# Photoreciever.net
KiCad netlist of a schematic drawn in Altium Designer
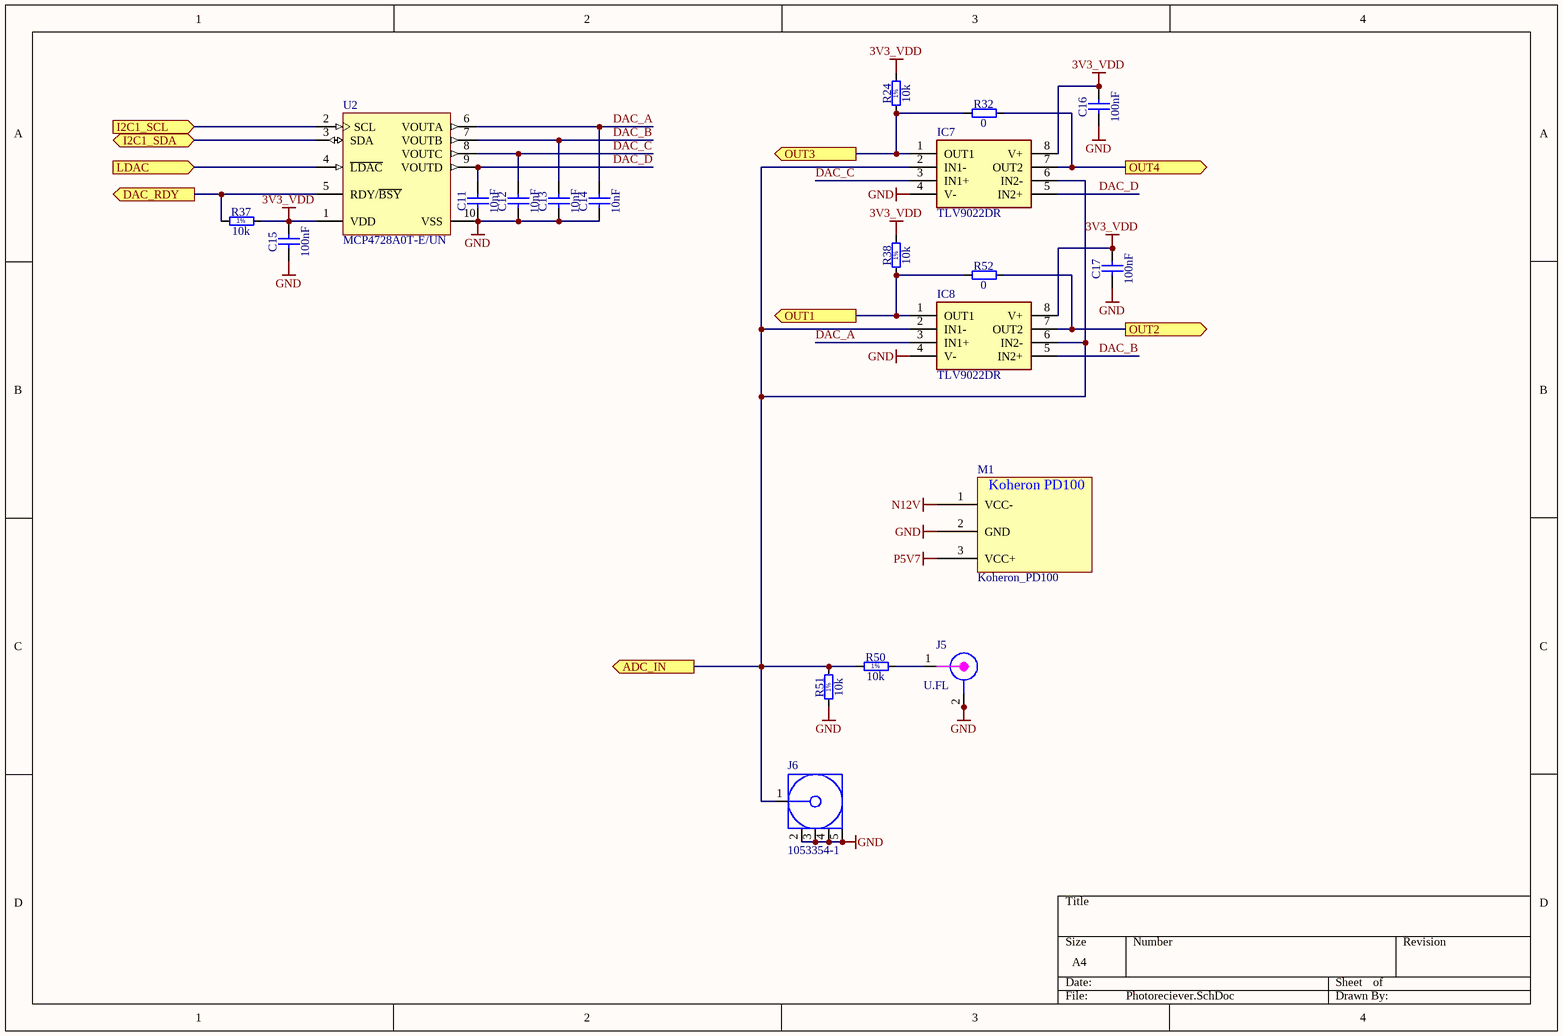
[diagram p0: Photoreciever.SchDoc]

(export (version "E")
  (design (tool "Eeschema 10.0.6"))
  (components
    (comp (ref "C11")
      (value "10nF")
      (footprint "CAPC1005X55N")
      (description "Non-polarised capacitor")
      (fields
        (field (name "PART NUMBER") "CC0402_10NF_16V_10%_X7R")
        (field (name "VOLTAGE") "16V")
        (field (name "AUTHOR") "CERN DEM JLC")
      )
      (libsource (lib "Capacitors") (part "Capacitor - non polarized"))
    )
    (comp (ref "C12")
      (value "10nF")
      (footprint "CAPC1005X55N")
      (description "Non-polarised capacitor")
      (fields
        (field (name "PART NUMBER") "CC0402_10NF_16V_10%_X7R")
        (field (name "VOLTAGE") "16V")
        (field (name "AUTHOR") "CERN DEM JLC")
      )
      (libsource (lib "Capacitors") (part "Capacitor - non polarized"))
    )
    (comp (ref "C13")
      (value "10nF")
      (footprint "CAPC1005X55N")
      (description "Non-polarised capacitor")
      (fields
        (field (name "PART NUMBER") "CC0402_10NF_16V_10%_X7R")
        (field (name "VOLTAGE") "16V")
        (field (name "AUTHOR") "CERN DEM JLC")
      )
      (libsource (lib "Capacitors") (part "Capacitor - non polarized"))
    )
    (comp (ref "C14")
      (value "10nF")
      (footprint "CAPC1005X55N")
      (description "Non-polarised capacitor")
      (fields
        (field (name "PART NUMBER") "CC0402_10NF_16V_10%_X7R")
        (field (name "VOLTAGE") "16V")
        (field (name "AUTHOR") "CERN DEM JLC")
      )
      (libsource (lib "Capacitors") (part "Capacitor - non polarized"))
    )
    (comp (ref "C15")
      (value "100nF")
      (footprint "CAPC1005X55N")
      (description "Non-polarised capacitor")
      (fields
        (field (name "PART NUMBER") "CC0402_100NF_16V_10%_X7R")
        (field (name "VOLTAGE") "16V")
        (field (name "AUTHOR") "CERN DEM JLC")
      )
      (libsource (lib "Capacitors") (part "Capacitor - non polarized"))
    )
    (comp (ref "C16")
      (value "100nF")
      (footprint "CAPC1005X55N")
      (description "Non-polarised capacitor")
      (fields
        (field (name "PART NUMBER") "CC0402_100NF_16V_10%_X7R")
        (field (name "VOLTAGE") "16V")
        (field (name "AUTHOR") "CERN DEM JLC")
      )
      (libsource (lib "Capacitors") (part "Capacitor - non polarized"))
    )
    (comp (ref "C17")
      (value "100nF")
      (footprint "CAPC1005X55N")
      (description "Non-polarised capacitor")
      (fields
        (field (name "PART NUMBER") "CC0402_100NF_16V_10%_X7R")
        (field (name "VOLTAGE") "16V")
        (field (name "AUTHOR") "CERN DEM JLC")
      )
      (libsource (lib "Capacitors") (part "Capacitor - non polarized"))
    )
    (comp (ref "IC7")
      (value "TLV9022DR")
      (footprint "SamacSys:SOIC127P600X175-8N")
      (description "Integrated Circuit")
      (libsource (lib "*") (part "TLV9022DR"))
    )
    (comp (ref "IC8")
      (value "TLV9022DR")
      (footprint "SamacSys:SOIC127P600X175-8N")
      (description "Integrated Circuit")
      (libsource (lib "*") (part "TLV9022DR"))
    )
    (comp (ref "J5")
      (value "U.FL")
      (footprint "CON_UFL_HIROSE_RECEPTACLE")
      (description "UFL")
      (libsource (lib "LIBRARY_SCH") (part "CON_UFL_SMD"))
    )
    (comp (ref "J6")
      (value "1053354-1")
      (footprint "TECO-1053354-1_V")
      (description "Female Coaxial Connector, Pitch 2.55 mm, Height 9.5 mm, Tail Length 3.9 mm, RoHS, Bulk")
      (fields (field (name "MANUFACTURER") "TE Connectivity"))
      (libsource (lib "Altium Content Vault") (part "CN-S-4F-RF5"))
    )
    (comp (ref "M1")
      (value "Koheron_PD100")
      (footprint "Koheron_PD100")
      (libsource (lib "MG_lib") (part "Koheron_PD100"))
    )
    (comp (ref "R24")
      (value "10k")
      (footprint "RESC1005X40N")
      (description "Resistor - 1%")
      (fields
        (field (name "PART NUMBER") "R0402_10K_1%_0.0625W_100PPM")
        (field (name "POWER") "0.0625W")
        (field (name "AUTHOR") "CERN DEM JLC")
      )
      (libsource (lib "Resistors") (part "Resistor - 1%"))
    )
    (comp (ref "R32")
      (value "0")
      (footprint "RESC1005X40N")
      (description "Resistor")
      (fields
        (field (name "PART NUMBER") "R0402_0R_JUMPER")
        (field (name "MANUFACTURER") "GENERIC")
        (field (name "AUTHOR") "CERN DEM JLC")
      )
      (libsource (lib "Resistors") (part "Resistor"))
    )
    (comp (ref "R37")
      (value "10k")
      (footprint "RESC1005X40N")
      (description "Resistor - 1%")
      (fields
        (field (name "PART NUMBER") "R0402_10K_1%_0.0625W_100PPM")
        (field (name "POWER") "0.0625W")
        (field (name "AUTHOR") "CERN DEM JLC")
      )
      (libsource (lib "Resistors") (part "Resistor - 1%"))
    )
    (comp (ref "R38")
      (value "10k")
      (footprint "RESC1005X40N")
      (description "Resistor - 1%")
      (fields
        (field (name "PART NUMBER") "R0402_10K_1%_0.0625W_100PPM")
        (field (name "POWER") "0.0625W")
        (field (name "AUTHOR") "CERN DEM JLC")
      )
      (libsource (lib "Resistors") (part "Resistor - 1%"))
    )
    (comp (ref "R50")
      (value "10k")
      (footprint "RESC1005X40N")
      (description "Resistor - 1%")
      (fields
        (field (name "PART NUMBER") "R0402_10K_1%_0.0625W_100PPM")
        (field (name "POWER") "0.0625W")
        (field (name "AUTHOR") "CERN DEM JLC")
      )
      (libsource (lib "Resistors") (part "Resistor - 1%"))
    )
    (comp (ref "R51")
      (value "10k")
      (footprint "RESC1005X40N")
      (description "Resistor - 1%")
      (fields
        (field (name "PART NUMBER") "R0402_10K_1%_0.0625W_100PPM")
        (field (name "POWER") "0.0625W")
        (field (name "AUTHOR") "CERN DEM JLC")
      )
      (libsource (lib "Resistors") (part "Resistor - 1%"))
    )
    (comp (ref "R52")
      (value "0")
      (footprint "RESC1005X40N")
      (description "Resistor")
      (fields
        (field (name "PART NUMBER") "R0402_0R_JUMPER")
        (field (name "MANUFACTURER") "GENERIC")
        (field (name "AUTHOR") "CERN DEM JLC")
      )
      (libsource (lib "Resistors") (part "Resistor"))
    )
    (comp (ref "U2")
      (value "MCP4728A0T-E/UN")
      (footprint "MSOP-UN10_M")
      (libsource (lib "Altium Content Vault") (part "CON-DAC-MCP4728-10"))
    )
  )
  (nets
    (net (code "1") (name "/ADC_IN") (class "Default")
      (node (ref "IC7") (pin "2") (pinfunction "IN1-_2") (pintype "passive"))
      (node (ref "IC7") (pin "6") (pinfunction "IN2-_6") (pintype "passive"))
      (node (ref "IC8") (pin "2") (pinfunction "IN1-_2") (pintype "passive"))
      (node (ref "IC8") (pin "6") (pinfunction "IN2-_6") (pintype "passive"))
      (node (ref "J6") (pin "1") (pinfunction "1_1") (pintype "passive"))
      (node (ref "R50") (pin "1") (pinfunction "1_1") (pintype "passive"))
      (node (ref "R51") (pin "2") (pinfunction "2_2") (pintype "passive"))
    )
    (net (code "2") (name "/DAC_A") (class "Default")
      (node (ref "C14") (pin "2") (pinfunction "2_2") (pintype "passive"))
      (node (ref "IC8") (pin "3") (pinfunction "IN1+_3") (pintype "passive"))
      (node (ref "U2") (pin "6") (pinfunction "VOUTA_6") (pintype "output"))
    )
    (net (code "3") (name "/DAC_B") (class "Default")
      (node (ref "C13") (pin "2") (pinfunction "2_2") (pintype "passive"))
      (node (ref "IC8") (pin "5") (pinfunction "IN2+_5") (pintype "passive"))
      (node (ref "U2") (pin "7") (pinfunction "VOUTB_7") (pintype "output"))
    )
    (net (code "4") (name "/DAC_C") (class "Default")
      (node (ref "C12") (pin "2") (pinfunction "2_2") (pintype "passive"))
      (node (ref "IC7") (pin "3") (pinfunction "IN1+_3") (pintype "passive"))
      (node (ref "U2") (pin "8") (pinfunction "VOUTC_8") (pintype "output"))
    )
    (net (code "5") (name "/DAC_D") (class "Default")
      (node (ref "C11") (pin "2") (pinfunction "2_2") (pintype "passive"))
      (node (ref "IC7") (pin "5") (pinfunction "IN2+_5") (pintype "passive"))
      (node (ref "U2") (pin "9") (pinfunction "VOUTD_9") (pintype "output"))
    )
    (net (code "6") (name "/DAC_RDY") (class "Default")
      (node (ref "R37") (pin "1") (pinfunction "1_1") (pintype "passive"))
      (node (ref "U2") (pin "5") (pinfunction "RDY/~{BSY}_5") (pintype "open_collector"))
    )
    (net (code "7") (name "/I2C1_SCL") (class "Default")
      (node (ref "U2") (pin "2") (pinfunction "SCL_2") (pintype "input"))
    )
    (net (code "8") (name "/I2C1_SDA") (class "Default")
      (node (ref "U2") (pin "3") (pinfunction "SDA_3") (pintype "bidirectional"))
    )
    (net (code "9") (name "/LDAC") (class "Default")
      (node (ref "U2") (pin "4") (pinfunction "~{LDAC}_4") (pintype "input"))
    )
    (net (code "10") (name "/OUT1") (class "Default")
      (node (ref "IC8") (pin "1") (pinfunction "OUT1_1") (pintype "passive"))
      (node (ref "R38") (pin "1") (pinfunction "1_1") (pintype "passive"))
      (node (ref "R52") (pin "1") (pinfunction "1_1") (pintype "passive"))
    )
    (net (code "11") (name "/OUT2") (class "Default")
      (node (ref "IC8") (pin "7") (pinfunction "OUT2_7") (pintype "passive"))
      (node (ref "R52") (pin "2") (pinfunction "2_2") (pintype "passive"))
    )
    (net (code "12") (name "/OUT3") (class "Default")
      (node (ref "IC7") (pin "1") (pinfunction "OUT1_1") (pintype "passive"))
      (node (ref "R24") (pin "1") (pinfunction "1_1") (pintype "passive"))
      (node (ref "R32") (pin "1") (pinfunction "1_1") (pintype "passive"))
    )
    (net (code "13") (name "/OUT4") (class "Default")
      (node (ref "IC7") (pin "7") (pinfunction "OUT2_7") (pintype "passive"))
      (node (ref "R32") (pin "2") (pinfunction "2_2") (pintype "passive"))
    )
    (net (code "14") (name "3V3_VDD") (class "Default")
      (node (ref "C15") (pin "2") (pinfunction "2_2") (pintype "passive"))
      (node (ref "C16") (pin "2") (pinfunction "2_2") (pintype "passive"))
      (node (ref "C17") (pin "2") (pinfunction "2_2") (pintype "passive"))
      (node (ref "IC7") (pin "8") (pinfunction "V+_8") (pintype "passive"))
      (node (ref "IC8") (pin "8") (pinfunction "V+_8") (pintype "passive"))
      (node (ref "R24") (pin "2") (pinfunction "2_2") (pintype "passive"))
      (node (ref "R37") (pin "2") (pinfunction "2_2") (pintype "passive"))
      (node (ref "R38") (pin "2") (pinfunction "2_2") (pintype "passive"))
      (node (ref "U2") (pin "1") (pinfunction "VDD_1") (pintype "power_in"))
    )
    (net (code "15") (name "GND") (class "Default")
      (node (ref "C11") (pin "1") (pinfunction "1_1") (pintype "passive"))
      (node (ref "C12") (pin "1") (pinfunction "1_1") (pintype "passive"))
      (node (ref "C13") (pin "1") (pinfunction "1_1") (pintype "passive"))
      (node (ref "C14") (pin "1") (pinfunction "1_1") (pintype "passive"))
      (node (ref "C15") (pin "1") (pinfunction "1_1") (pintype "passive"))
      (node (ref "C16") (pin "1") (pinfunction "1_1") (pintype "passive"))
      (node (ref "C17") (pin "1") (pinfunction "1_1") (pintype "passive"))
      (node (ref "IC7") (pin "4") (pinfunction "V-_4") (pintype "passive"))
      (node (ref "IC8") (pin "4") (pinfunction "V-_4") (pintype "passive"))
      (node (ref "J5") (pin "2") (pintype "passive"))
      (node (ref "J5") (pin "2a") (pinfunction "GND_2a") (pintype "passive"))
      (node (ref "J6") (pin "2") (pinfunction "2_2") (pintype "passive"))
      (node (ref "J6") (pin "3") (pinfunction "3_3") (pintype "passive"))
      (node (ref "J6") (pin "4") (pinfunction "4_4") (pintype "passive"))
      (node (ref "J6") (pin "5") (pinfunction "5_5") (pintype "passive"))
      (node (ref "M1") (pin "2") (pinfunction "GND_2") (pintype "passive"))
      (node (ref "R51") (pin "1") (pinfunction "1_1") (pintype "passive"))
      (node (ref "U2") (pin "10") (pinfunction "VSS_10") (pintype "power_in"))
    )
    (net (code "16") (name "N12V") (class "Default")
      (node (ref "M1") (pin "1") (pinfunction "VCC-_1") (pintype "passive"))
    )
    (net (code "17") (name "Net-(J5-Pad1)") (class "Default")
      (node (ref "J5") (pin "1") (pintype "passive"))
      (node (ref "R50") (pin "2") (pinfunction "2_2") (pintype "passive"))
    )
    (net (code "18") (name "P5V7") (class "Default")
      (node (ref "M1") (pin "3") (pinfunction "VCC+_3") (pintype "passive"))
    )
  )
)
